# untitledunfinished.net
KiCad netlist of a schematic drawn in EAGLE
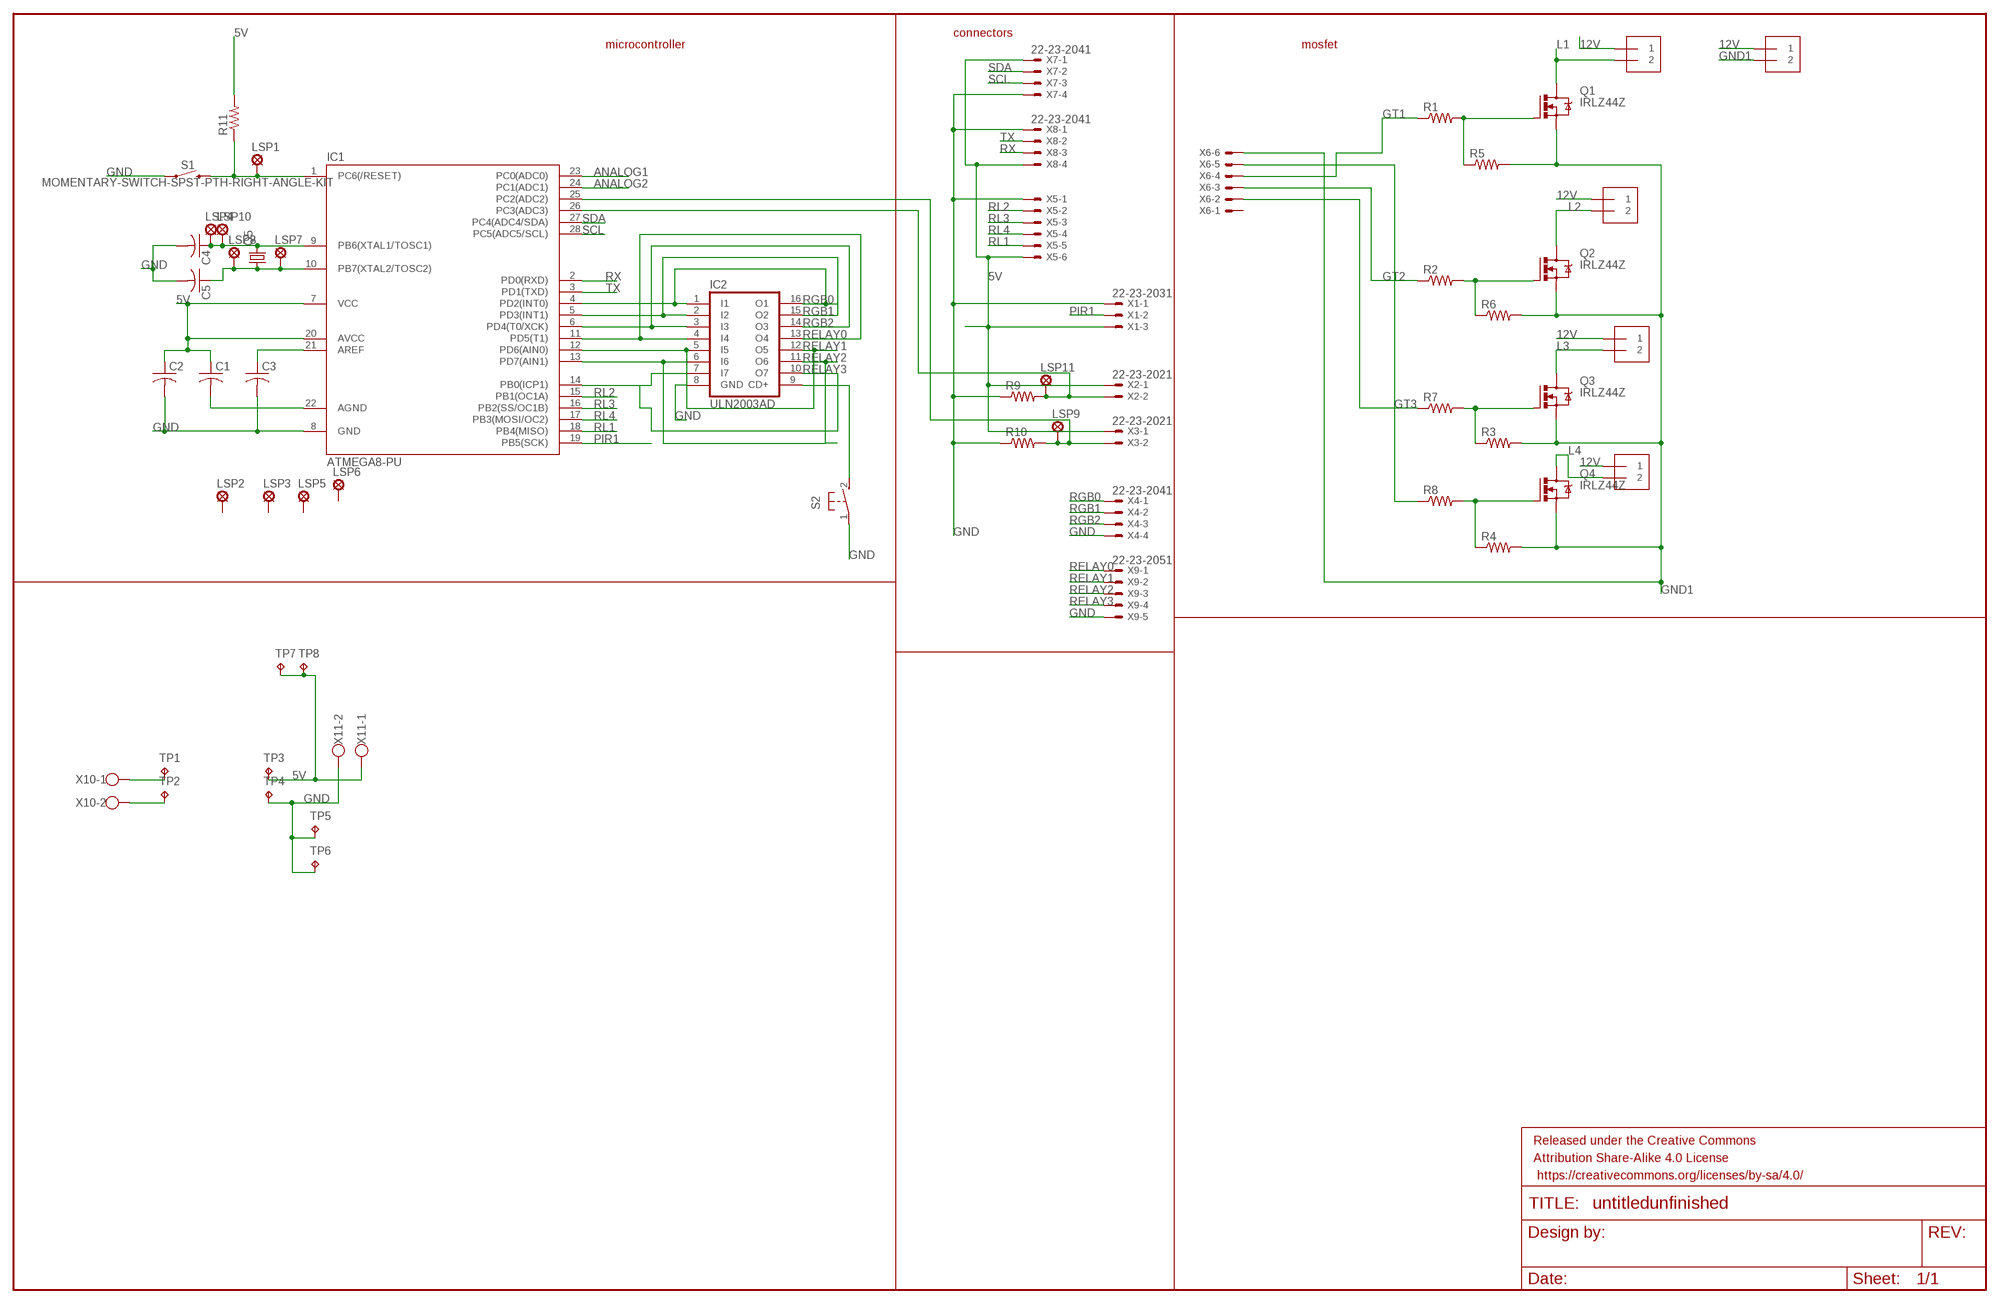
[diagram p0: schematic, sheet 1]

(export (version "E")
  (design (tool "Eeschema 10.0.6"))
  (components
    (comp (ref "C1")
      (value "C-US050-025X075")
      (footprint "eagle-import:C050-025X075")
      (libsource (lib "eagle-import") (part "C-US050-025X075"))
    )
    (comp (ref "C2")
      (value "C-US050-025X075")
      (footprint "eagle-import:C050-025X075")
      (libsource (lib "eagle-import") (part "C-US050-025X075"))
    )
    (comp (ref "C3")
      (value "C-US050-025X075")
      (footprint "eagle-import:C050-025X075")
      (libsource (lib "eagle-import") (part "C-US050-025X075"))
    )
    (comp (ref "C4")
      (value "C-US050-024X044")
      (footprint "eagle-import:C050-024X044")
      (libsource (lib "eagle-import") (part "C-US050-024X044"))
    )
    (comp (ref "C5")
      (value "C-US050-024X044")
      (footprint "eagle-import:C050-024X044")
      (libsource (lib "eagle-import") (part "C-US050-024X044"))
    )
    (comp (ref "FRAME1")
      (value "FRAME-LEDGER")
      (footprint "eagle-import:CREATIVE_COMMONS")
      (libsource (lib "eagle-import") (part "FRAME-LEDGER"))
    )
    (comp (ref "IC1")
      (value "ATMEGA8-PU")
      (footprint "eagle-import:DIL28-3")
      (libsource (lib "eagle-import") (part "ATMEGA8-PU"))
    )
    (comp (ref "IC2")
      (value "ULN2003AD")
      (footprint "eagle-import:SO16")
      (libsource (lib "eagle-import") (part "ULN2003AD"))
    )
    (comp (ref "J1")
      (value "1X2-3.5MM")
      (footprint "eagle-import:1X2-3.5MM")
      (libsource (lib "eagle-import") (part "1X2-3.5MM"))
    )
    (comp (ref "J2")
      (value "1X2-3.5MM")
      (footprint "eagle-import:1X2-3.5MM")
      (libsource (lib "eagle-import") (part "1X2-3.5MM"))
    )
    (comp (ref "J3")
      (value "1X2-3.5MM")
      (footprint "eagle-import:1X2-3.5MM")
      (libsource (lib "eagle-import") (part "1X2-3.5MM"))
    )
    (comp (ref "J4")
      (value "1X2-3.5MM")
      (footprint "eagle-import:1X2-3.5MM")
      (libsource (lib "eagle-import") (part "1X2-3.5MM"))
    )
    (comp (ref "J5")
      (value "1X2-3.5MM")
      (footprint "eagle-import:1X2-3.5MM")
      (libsource (lib "eagle-import") (part "1X2-3.5MM"))
    )
    (comp (ref "LSP1")
      (value "SE11")
      (footprint "eagle-import:SE11")
      (libsource (lib "eagle-import") (part "SE11"))
    )
    (comp (ref "LSP2")
      (value "SE11")
      (footprint "eagle-import:SE11")
      (libsource (lib "eagle-import") (part "SE11"))
    )
    (comp (ref "LSP3")
      (value "SE11")
      (footprint "eagle-import:SE11")
      (libsource (lib "eagle-import") (part "SE11"))
    )
    (comp (ref "LSP4")
      (value "SE11")
      (footprint "eagle-import:SE11")
      (libsource (lib "eagle-import") (part "SE11"))
    )
    (comp (ref "LSP5")
      (value "SE11")
      (footprint "eagle-import:SE11")
      (libsource (lib "eagle-import") (part "SE11"))
    )
    (comp (ref "LSP6")
      (value "SE11")
      (footprint "eagle-import:SE11")
      (libsource (lib "eagle-import") (part "SE11"))
    )
    (comp (ref "LSP7")
      (value "SE11")
      (footprint "eagle-import:SE11")
      (libsource (lib "eagle-import") (part "SE11"))
    )
    (comp (ref "LSP8")
      (value "SE11")
      (footprint "eagle-import:SE11")
      (libsource (lib "eagle-import") (part "SE11"))
    )
    (comp (ref "LSP9")
      (value "SE11")
      (footprint "eagle-import:SE11")
      (libsource (lib "eagle-import") (part "SE11"))
    )
    (comp (ref "LSP10")
      (value "SE11")
      (footprint "eagle-import:SE11")
      (libsource (lib "eagle-import") (part "SE11"))
    )
    (comp (ref "LSP11")
      (value "SE11")
      (footprint "eagle-import:SE11")
      (libsource (lib "eagle-import") (part "SE11"))
    )
    (comp (ref "Q1")
      (value "IRLZ44Z")
      (footprint "eagle-import:TO220BH")
      (libsource (lib "eagle-import") (part "IRLZ44Z"))
    )
    (comp (ref "Q2")
      (value "IRLZ44Z")
      (footprint "eagle-import:TO220BH")
      (libsource (lib "eagle-import") (part "IRLZ44Z"))
    )
    (comp (ref "Q3")
      (value "IRLZ44Z")
      (footprint "eagle-import:TO220BH")
      (libsource (lib "eagle-import") (part "IRLZ44Z"))
    )
    (comp (ref "Q4")
      (value "IRLZ44Z")
      (footprint "eagle-import:TO220BH")
      (libsource (lib "eagle-import") (part "IRLZ44Z"))
    )
    (comp (ref "Q5")
      (value "CRYSTALHC49U-V")
      (footprint "eagle-import:HC49U-V")
      (libsource (lib "eagle-import") (part "CRYSTALHC49U-V"))
    )
    (comp (ref "R1")
      (value "R-US_0207/10")
      (footprint "eagle-import:0207_10")
      (libsource (lib "eagle-import") (part "R-US_0207/10"))
    )
    (comp (ref "R2")
      (value "R-US_0207/10")
      (footprint "eagle-import:0207_10")
      (libsource (lib "eagle-import") (part "R-US_0207/10"))
    )
    (comp (ref "R3")
      (value "R-US_0207/10")
      (footprint "eagle-import:0207_10")
      (libsource (lib "eagle-import") (part "R-US_0207/10"))
    )
    (comp (ref "R4")
      (value "R-US_0207/10")
      (footprint "eagle-import:0207_10")
      (libsource (lib "eagle-import") (part "R-US_0207/10"))
    )
    (comp (ref "R5")
      (value "R-US_0207/10")
      (footprint "eagle-import:0207_10")
      (libsource (lib "eagle-import") (part "R-US_0207/10"))
    )
    (comp (ref "R6")
      (value "R-US_0207/10")
      (footprint "eagle-import:0207_10")
      (libsource (lib "eagle-import") (part "R-US_0207/10"))
    )
    (comp (ref "R7")
      (value "R-US_0207/10")
      (footprint "eagle-import:0207_10")
      (libsource (lib "eagle-import") (part "R-US_0207/10"))
    )
    (comp (ref "R8")
      (value "R-US_0207/10")
      (footprint "eagle-import:0207_10")
      (libsource (lib "eagle-import") (part "R-US_0207/10"))
    )
    (comp (ref "R9")
      (value "R-US_0207/15")
      (footprint "eagle-import:0207_15")
      (libsource (lib "eagle-import") (part "R-US_0207/15"))
    )
    (comp (ref "R10")
      (value "R-US_0207/15")
      (footprint "eagle-import:0207_15")
      (libsource (lib "eagle-import") (part "R-US_0207/15"))
    )
    (comp (ref "R11")
      (value "R-US_0207/10")
      (footprint "eagle-import:0207_10")
      (libsource (lib "eagle-import") (part "R-US_0207/10"))
    )
    (comp (ref "S1")
      (value "MOMENTARY-SWITCH-SPST-PTH-RIGHT-ANGLE-KIT")
      (footprint "eagle-import:TACTILE_SWITCH_PTH_RIGHT_ANGLE_KIT")
      (libsource (lib "eagle-import") (part "MOMENTARY-SWITCH-SPST-PTH-RIGHT-ANGLE-KIT"))
    )
    (comp (ref "S2")
      (value "31-XX")
      (footprint "eagle-import:B3F-31XX")
      (libsource (lib "eagle-import") (part "31-XX"))
    )
    (comp (ref "TP1")
      (value "TPPAD1-20Y")
      (footprint "eagle-import:P1-20Y")
      (libsource (lib "eagle-import") (part "TPPAD1-20Y"))
    )
    (comp (ref "TP2")
      (value "TPPAD1-20Y")
      (footprint "eagle-import:P1-20Y")
      (libsource (lib "eagle-import") (part "TPPAD1-20Y"))
    )
    (comp (ref "TP3")
      (value "TPPAD1-20Y")
      (footprint "eagle-import:P1-20Y")
      (libsource (lib "eagle-import") (part "TPPAD1-20Y"))
    )
    (comp (ref "TP4")
      (value "TPPAD1-20Y")
      (footprint "eagle-import:P1-20Y")
      (libsource (lib "eagle-import") (part "TPPAD1-20Y"))
    )
    (comp (ref "TP5")
      (value "TPPAD1-13Y")
      (footprint "eagle-import:P1-13Y")
      (libsource (lib "eagle-import") (part "TPPAD1-13Y"))
    )
    (comp (ref "TP6")
      (value "TPPAD1-13Y")
      (footprint "eagle-import:P1-13Y")
      (libsource (lib "eagle-import") (part "TPPAD1-13Y"))
    )
    (comp (ref "TP7")
      (value "TPPAD1-13Y")
      (footprint "eagle-import:P1-13Y")
      (libsource (lib "eagle-import") (part "TPPAD1-13Y"))
    )
    (comp (ref "TP8")
      (value "TPPAD1-13Y")
      (footprint "eagle-import:P1-13Y")
      (libsource (lib "eagle-import") (part "TPPAD1-13Y"))
    )
    (comp (ref "X1")
      (value "22-23-2031")
      (footprint "eagle-import:22-23-2031")
      (fields (field (name "MF") "MOLEX"))
      (libsource (lib "eagle-import") (part "22-23-2031"))
    )
    (comp (ref "X2")
      (value "22-23-2021")
      (footprint "eagle-import:22-23-2021")
      (fields (field (name "MF") "MOLEX"))
      (libsource (lib "eagle-import") (part "22-23-2021"))
    )
    (comp (ref "X3")
      (value "22-23-2021")
      (footprint "eagle-import:22-23-2021")
      (fields (field (name "MF") "MOLEX"))
      (libsource (lib "eagle-import") (part "22-23-2021"))
    )
    (comp (ref "X4")
      (value "22-23-2041")
      (footprint "eagle-import:22-23-2041")
      (fields (field (name "MF") "MOLEX"))
      (libsource (lib "eagle-import") (part "22-23-2041"))
    )
    (comp (ref "X5")
      (value "22-23-2061")
      (footprint "eagle-import:22-23-2061")
      (fields (field (name "MF") "MOLEX"))
      (libsource (lib "eagle-import") (part "22-23-2061"))
    )
    (comp (ref "X6")
      (value "22-23-2061")
      (footprint "eagle-import:22-23-2061")
      (fields (field (name "MF") "MOLEX"))
      (libsource (lib "eagle-import") (part "22-23-2061"))
    )
    (comp (ref "X7")
      (value "22-23-2041")
      (footprint "eagle-import:22-23-2041")
      (fields (field (name "MF") "MOLEX"))
      (libsource (lib "eagle-import") (part "22-23-2041"))
    )
    (comp (ref "X8")
      (value "22-23-2041")
      (footprint "eagle-import:22-23-2041")
      (fields (field (name "MF") "MOLEX"))
      (libsource (lib "eagle-import") (part "22-23-2041"))
    )
    (comp (ref "X9")
      (value "22-23-2051")
      (footprint "eagle-import:22-23-2051")
      (fields (field (name "MF") "MOLEX"))
      (libsource (lib "eagle-import") (part "22-23-2051"))
    )
    (comp (ref "X10")
      (value "W237-102")
      (footprint "eagle-import:W237-102")
      (fields (field (name "MPN") "237-102"))
      (libsource (lib "eagle-import") (part "W237-102"))
    )
    (comp (ref "X11")
      (value "W237-102")
      (footprint "eagle-import:W237-102")
      (fields (field (name "MPN") "237-102"))
      (libsource (lib "eagle-import") (part "W237-102"))
    )
  )
  (nets
    (net (code "1") (name "/5V") (class "Default")
      (node (ref "C1") (pin "1") (pinfunction "1_1") (pintype "passive"))
      (node (ref "C2") (pin "1") (pinfunction "1_1") (pintype "passive"))
      (node (ref "IC1") (pin "20") (pinfunction "AVCC_20") (pintype "passive"))
      (node (ref "IC1") (pin "7") (pinfunction "VCC_7") (pintype "power_in"))
      (node (ref "R11") (pin "2") (pinfunction "2_2") (pintype "passive"))
      (node (ref "TP3") (pin "TP") (pinfunction "TP_TP") (pintype "input"))
      (node (ref "TP7") (pin "TP") (pinfunction "TP_TP") (pintype "input"))
      (node (ref "TP8") (pin "TP") (pinfunction "TP_TP") (pintype "input"))
      (node (ref "X1") (pin "3") (pinfunction "S_3") (pintype "passive"))
      (node (ref "X11") (pin "1") (pinfunction "KL_1") (pintype "passive"))
      (node (ref "X2") (pin "1") (pinfunction "S_1") (pintype "passive"))
      (node (ref "X3") (pin "1") (pinfunction "S_1") (pintype "passive"))
      (node (ref "X5") (pin "6") (pinfunction "S_6") (pintype "passive"))
      (node (ref "X7") (pin "1") (pinfunction "S_1") (pintype "passive"))
      (node (ref "X8") (pin "4") (pinfunction "S_4") (pintype "passive"))
    )
    (net (code "2") (name "/12V") (class "Default")
      (node (ref "J1") (pin "1") (pinfunction "1_1") (pintype "passive"))
      (node (ref "J2") (pin "1") (pinfunction "1_1") (pintype "passive"))
      (node (ref "J3") (pin "1") (pinfunction "1_1") (pintype "passive"))
      (node (ref "J4") (pin "1") (pinfunction "1_1") (pintype "passive"))
      (node (ref "J5") (pin "1") (pinfunction "1_1") (pintype "passive"))
    )
    (net (code "3") (name "/ANALOG1") (class "Default")
      (node (ref "IC1") (pin "23") (pinfunction "PC0(ADC0)_23") (pintype "bidirectional"))
    )
    (net (code "4") (name "/ANALOG2") (class "Default")
      (node (ref "IC1") (pin "24") (pinfunction "PC1(ADC1)_24") (pintype "bidirectional"))
    )
    (net (code "5") (name "/GND") (class "Default")
      (node (ref "C2") (pin "2") (pinfunction "2_2") (pintype "passive"))
      (node (ref "C3") (pin "2") (pinfunction "2_2") (pintype "passive"))
      (node (ref "C4") (pin "2") (pinfunction "2_2") (pintype "passive"))
      (node (ref "C5") (pin "2") (pinfunction "2_2") (pintype "passive"))
      (node (ref "IC1") (pin "8") (pinfunction "GND_8") (pintype "power_in"))
      (node (ref "IC2") (pin "8") (pinfunction "GND_8") (pintype "power_in"))
      (node (ref "R10") (pin "1") (pinfunction "1_1") (pintype "passive"))
      (node (ref "R9") (pin "1") (pinfunction "1_1") (pintype "passive"))
      (node (ref "S1") (pin "1") (pinfunction "1_1") (pintype "passive"))
      (node (ref "S2") (pin "1") (pinfunction "P_1") (pintype "passive"))
      (node (ref "TP4") (pin "TP") (pinfunction "TP_TP") (pintype "input"))
      (node (ref "TP5") (pin "TP") (pinfunction "TP_TP") (pintype "input"))
      (node (ref "TP6") (pin "TP") (pinfunction "TP_TP") (pintype "input"))
      (node (ref "X1") (pin "1") (pinfunction "S_1") (pintype "passive"))
      (node (ref "X11") (pin "2") (pinfunction "KL_2") (pintype "passive"))
      (node (ref "X4") (pin "4") (pinfunction "S_4") (pintype "passive"))
      (node (ref "X5") (pin "1") (pinfunction "S_1") (pintype "passive"))
      (node (ref "X7") (pin "4") (pinfunction "S_4") (pintype "passive"))
      (node (ref "X8") (pin "1") (pinfunction "S_1") (pintype "passive"))
      (node (ref "X9") (pin "5") (pinfunction "S_5") (pintype "passive"))
    )
    (net (code "6") (name "/GND1") (class "Default")
      (node (ref "J5") (pin "2") (pinfunction "2_2") (pintype "passive"))
      (node (ref "Q1") (pin "S") (pinfunction "S_S") (pintype "passive"))
      (node (ref "Q2") (pin "S") (pinfunction "S_S") (pintype "passive"))
      (node (ref "Q3") (pin "S") (pinfunction "S_S") (pintype "passive"))
      (node (ref "Q4") (pin "S") (pinfunction "S_S") (pintype "passive"))
      (node (ref "R3") (pin "2") (pinfunction "2_2") (pintype "passive"))
      (node (ref "R4") (pin "2") (pinfunction "2_2") (pintype "passive"))
      (node (ref "R5") (pin "2") (pinfunction "2_2") (pintype "passive"))
      (node (ref "R6") (pin "2") (pinfunction "2_2") (pintype "passive"))
      (node (ref "X6") (pin "6") (pinfunction "S_6") (pintype "passive"))
    )
    (net (code "7") (name "/GT1") (class "Default")
      (node (ref "R1") (pin "1") (pinfunction "1_1") (pintype "passive"))
      (node (ref "X6") (pin "4") (pinfunction "S_4") (pintype "passive"))
    )
    (net (code "8") (name "/GT2") (class "Default")
      (node (ref "R2") (pin "1") (pinfunction "1_1") (pintype "passive"))
      (node (ref "X6") (pin "3") (pinfunction "S_3") (pintype "passive"))
    )
    (net (code "9") (name "/GT3") (class "Default")
      (node (ref "R7") (pin "1") (pinfunction "1_1") (pintype "passive"))
      (node (ref "X6") (pin "2") (pinfunction "S_2") (pintype "passive"))
    )
    (net (code "10") (name "/L1") (class "Default")
      (node (ref "J1") (pin "2") (pinfunction "2_2") (pintype "passive"))
      (node (ref "Q1") (pin "D") (pinfunction "D_D") (pintype "passive"))
    )
    (net (code "11") (name "/L2") (class "Default")
      (node (ref "J2") (pin "2") (pinfunction "2_2") (pintype "passive"))
      (node (ref "Q2") (pin "D") (pinfunction "D_D") (pintype "passive"))
    )
    (net (code "12") (name "/L3") (class "Default")
      (node (ref "J3") (pin "2") (pinfunction "2_2") (pintype "passive"))
      (node (ref "Q3") (pin "D") (pinfunction "D_D") (pintype "passive"))
    )
    (net (code "13") (name "/L4") (class "Default")
      (node (ref "J4") (pin "2") (pinfunction "2_2") (pintype "passive"))
      (node (ref "Q4") (pin "D") (pinfunction "D_D") (pintype "passive"))
    )
    (net (code "14") (name "/PIR1") (class "Default")
      (node (ref "IC1") (pin "19") (pinfunction "PB5(SCK)_19") (pintype "bidirectional"))
      (node (ref "X1") (pin "2") (pinfunction "S_2") (pintype "passive"))
    )
    (net (code "15") (name "/RELAY0") (class "Default")
      (node (ref "IC1") (pin "11") (pinfunction "PD5(T1)_11") (pintype "bidirectional"))
      (node (ref "IC2") (pin "13") (pinfunction "O4_13") (pintype "open_collector"))
      (node (ref "IC2") (pin "4") (pinfunction "I4_4") (pintype "input"))
      (node (ref "X9") (pin "1") (pinfunction "S_1") (pintype "passive"))
    )
    (net (code "16") (name "/RELAY1") (class "Default")
      (node (ref "IC1") (pin "12") (pinfunction "PD6(AIN0)_12") (pintype "bidirectional"))
      (node (ref "IC2") (pin "12") (pinfunction "O5_12") (pintype "open_collector"))
      (node (ref "IC2") (pin "5") (pinfunction "I5_5") (pintype "input"))
      (node (ref "X9") (pin "2") (pinfunction "S_2") (pintype "passive"))
    )
    (net (code "17") (name "/RELAY2") (class "Default")
      (node (ref "IC1") (pin "13") (pinfunction "PD7(AIN1)_13") (pintype "bidirectional"))
      (node (ref "IC2") (pin "11") (pinfunction "O6_11") (pintype "open_collector"))
      (node (ref "IC2") (pin "6") (pinfunction "I6_6") (pintype "input"))
      (node (ref "X9") (pin "3") (pinfunction "S_3") (pintype "passive"))
    )
    (net (code "18") (name "/RELAY3") (class "Default")
      (node (ref "IC1") (pin "14") (pinfunction "PB0(ICP1)_14") (pintype "bidirectional"))
      (node (ref "IC2") (pin "10") (pinfunction "O7_10") (pintype "open_collector"))
      (node (ref "IC2") (pin "7") (pinfunction "I7_7") (pintype "input"))
      (node (ref "X9") (pin "4") (pinfunction "S_4") (pintype "passive"))
    )
    (net (code "19") (name "/RGB0") (class "Default")
      (node (ref "IC1") (pin "4") (pinfunction "PD2(INT0)_4") (pintype "bidirectional"))
      (node (ref "IC2") (pin "1") (pinfunction "I1_1") (pintype "input"))
      (node (ref "IC2") (pin "16") (pinfunction "O1_16") (pintype "open_collector"))
      (node (ref "X4") (pin "1") (pinfunction "S_1") (pintype "passive"))
    )
    (net (code "20") (name "/RGB1") (class "Default")
      (node (ref "IC1") (pin "5") (pinfunction "PD3(INT1)_5") (pintype "bidirectional"))
      (node (ref "IC2") (pin "15") (pinfunction "O2_15") (pintype "open_collector"))
      (node (ref "IC2") (pin "2") (pinfunction "I2_2") (pintype "input"))
      (node (ref "X4") (pin "2") (pinfunction "S_2") (pintype "passive"))
    )
    (net (code "21") (name "/RGB2") (class "Default")
      (node (ref "IC1") (pin "6") (pinfunction "PD4(T0/XCK)_6") (pintype "bidirectional"))
      (node (ref "IC2") (pin "14") (pinfunction "O3_14") (pintype "open_collector"))
      (node (ref "IC2") (pin "3") (pinfunction "I3_3") (pintype "input"))
      (node (ref "X4") (pin "3") (pinfunction "S_3") (pintype "passive"))
    )
    (net (code "22") (name "/RL1") (class "Default")
      (node (ref "IC1") (pin "18") (pinfunction "PB4(MISO)_18") (pintype "bidirectional"))
      (node (ref "X5") (pin "5") (pinfunction "S_5") (pintype "passive"))
    )
    (net (code "23") (name "/RL2") (class "Default")
      (node (ref "IC1") (pin "15") (pinfunction "PB1(OC1A)_15") (pintype "bidirectional"))
      (node (ref "X5") (pin "2") (pinfunction "S_2") (pintype "passive"))
    )
    (net (code "24") (name "/RL3") (class "Default")
      (node (ref "IC1") (pin "16") (pinfunction "PB2(SS/OC1B)_16") (pintype "bidirectional"))
      (node (ref "X5") (pin "3") (pinfunction "S_3") (pintype "passive"))
    )
    (net (code "25") (name "/RL4") (class "Default")
      (node (ref "IC1") (pin "17") (pinfunction "PB3(MOSI/OC2)_17") (pintype "bidirectional"))
      (node (ref "X5") (pin "4") (pinfunction "S_4") (pintype "passive"))
    )
    (net (code "26") (name "/RX") (class "Default")
      (node (ref "IC1") (pin "2") (pinfunction "PD0(RXD)_2") (pintype "bidirectional"))
      (node (ref "X8") (pin "3") (pinfunction "S_3") (pintype "passive"))
    )
    (net (code "27") (name "/SCL") (class "Default")
      (node (ref "IC1") (pin "28") (pinfunction "PC5(ADC5/SCL)_28") (pintype "bidirectional"))
      (node (ref "X7") (pin "3") (pinfunction "S_3") (pintype "passive"))
    )
    (net (code "28") (name "/SDA") (class "Default")
      (node (ref "IC1") (pin "27") (pinfunction "PC4(ADC4/SDA)_27") (pintype "bidirectional"))
      (node (ref "X7") (pin "2") (pinfunction "S_2") (pintype "passive"))
    )
    (net (code "29") (name "/TX") (class "Default")
      (node (ref "IC1") (pin "3") (pinfunction "PD1(TXD)_3") (pintype "bidirectional"))
      (node (ref "X8") (pin "2") (pinfunction "S_2") (pintype "passive"))
    )
    (net (code "30") (name "Net-(IC1-AGND)") (class "Default")
      (node (ref "C1") (pin "2") (pinfunction "2_2") (pintype "passive"))
      (node (ref "IC1") (pin "22") (pinfunction "AGND_22") (pintype "power_in"))
    )
    (net (code "31") (name "Net-(IC1-AREF)") (class "Default")
      (node (ref "C3") (pin "1") (pinfunction "1_1") (pintype "passive"))
      (node (ref "IC1") (pin "21") (pinfunction "AREF_21") (pintype "passive"))
    )
    (net (code "32") (name "Net-(IC1-PB6(XTAL1{slash}TOSC1))") (class "Default")
      (node (ref "C4") (pin "1") (pinfunction "1_1") (pintype "passive"))
      (node (ref "IC1") (pin "9") (pinfunction "PB6(XTAL1/TOSC1)_9") (pintype "bidirectional"))
      (node (ref "LSP10") (pin "MP") (pinfunction "MP_MP") (pintype "passive"))
      (node (ref "LSP4") (pin "MP") (pinfunction "MP_MP") (pintype "passive"))
      (node (ref "Q5") (pin "2") (pinfunction "2_2") (pintype "passive"))
    )
    (net (code "33") (name "Net-(IC1-PB7(XTAL2{slash}TOSC2))") (class "Default")
      (node (ref "C5") (pin "1") (pinfunction "1_1") (pintype "passive"))
      (node (ref "IC1") (pin "10") (pinfunction "PB7(XTAL2/TOSC2)_10") (pintype "bidirectional"))
      (node (ref "LSP7") (pin "MP") (pinfunction "MP_MP") (pintype "passive"))
      (node (ref "LSP8") (pin "MP") (pinfunction "MP_MP") (pintype "passive"))
      (node (ref "Q5") (pin "1") (pinfunction "1_1") (pintype "passive"))
    )
    (net (code "34") (name "Net-(IC1-PC2(ADC2))") (class "Default")
      (node (ref "IC1") (pin "25") (pinfunction "PC2(ADC2)_25") (pintype "bidirectional"))
      (node (ref "LSP9") (pin "MP") (pinfunction "MP_MP") (pintype "passive"))
      (node (ref "R10") (pin "2") (pinfunction "2_2") (pintype "passive"))
      (node (ref "X3") (pin "2") (pinfunction "S_2") (pintype "passive"))
    )
    (net (code "35") (name "Net-(IC1-PC3(ADC3))") (class "Default")
      (node (ref "IC1") (pin "26") (pinfunction "PC3(ADC3)_26") (pintype "bidirectional"))
      (node (ref "LSP11") (pin "MP") (pinfunction "MP_MP") (pintype "passive"))
      (node (ref "R9") (pin "2") (pinfunction "2_2") (pintype "passive"))
      (node (ref "X2") (pin "2") (pinfunction "S_2") (pintype "passive"))
    )
    (net (code "36") (name "Net-(IC1-PC6({slash}RESET))") (class "Default")
      (node (ref "IC1") (pin "1") (pinfunction "PC6(/RESET)_1") (pintype "bidirectional"))
      (node (ref "LSP1") (pin "MP") (pinfunction "MP_MP") (pintype "passive"))
      (node (ref "R11") (pin "1") (pinfunction "1_1") (pintype "passive"))
      (node (ref "S1") (pin "2") (pinfunction "2_2") (pintype "passive"))
    )
    (net (code "37") (name "Net-(IC2-CD+)") (class "Default")
      (node (ref "IC2") (pin "9") (pinfunction "CD+_9") (pintype "passive"))
      (node (ref "S2") (pin "2") (pinfunction "S_2") (pintype "passive"))
    )
    (net (code "38") (name "Net-(Q1-PadG)") (class "Default")
      (node (ref "Q1") (pin "G") (pinfunction "G_G") (pintype "passive"))
      (node (ref "R1") (pin "2") (pinfunction "2_2") (pintype "passive"))
      (node (ref "R5") (pin "1") (pinfunction "1_1") (pintype "passive"))
    )
    (net (code "39") (name "Net-(Q2-PadG)") (class "Default")
      (node (ref "Q2") (pin "G") (pinfunction "G_G") (pintype "passive"))
      (node (ref "R2") (pin "2") (pinfunction "2_2") (pintype "passive"))
      (node (ref "R6") (pin "1") (pinfunction "1_1") (pintype "passive"))
    )
    (net (code "40") (name "Net-(Q3-PadG)") (class "Default")
      (node (ref "Q3") (pin "G") (pinfunction "G_G") (pintype "passive"))
      (node (ref "R3") (pin "1") (pinfunction "1_1") (pintype "passive"))
      (node (ref "R7") (pin "2") (pinfunction "2_2") (pintype "passive"))
    )
    (net (code "41") (name "Net-(Q4-PadG)") (class "Default")
      (node (ref "Q4") (pin "G") (pinfunction "G_G") (pintype "passive"))
      (node (ref "R4") (pin "1") (pinfunction "1_1") (pintype "passive"))
      (node (ref "R8") (pin "2") (pinfunction "2_2") (pintype "passive"))
    )
    (net (code "42") (name "Net-(X6E-S)") (class "Default")
      (node (ref "R8") (pin "1") (pinfunction "1_1") (pintype "passive"))
      (node (ref "X6") (pin "5") (pinfunction "S_5") (pintype "passive"))
    )
    (net (code "43") (name "Net-(X10A-KL)") (class "Default")
      (node (ref "TP1") (pin "TP") (pinfunction "TP_TP") (pintype "input"))
      (node (ref "X10") (pin "1") (pinfunction "KL_1") (pintype "passive"))
    )
    (net (code "44") (name "Net-(X10B-KL)") (class "Default")
      (node (ref "TP2") (pin "TP") (pinfunction "TP_TP") (pintype "input"))
      (node (ref "X10") (pin "2") (pinfunction "KL_2") (pintype "passive"))
    )
    (net (code "45") (name "unconnected-(LSP2-PadMP)") (class "Default")
      (node (ref "LSP2") (pin "MP") (pinfunction "MP_MP") (pintype "passive"))
    )
    (net (code "46") (name "unconnected-(LSP3-PadMP)") (class "Default")
      (node (ref "LSP3") (pin "MP") (pinfunction "MP_MP") (pintype "passive"))
    )
    (net (code "47") (name "unconnected-(LSP5-PadMP)") (class "Default")
      (node (ref "LSP5") (pin "MP") (pinfunction "MP_MP") (pintype "passive"))
    )
    (net (code "48") (name "unconnected-(LSP6-PadMP)") (class "Default")
      (node (ref "LSP6") (pin "MP") (pinfunction "MP_MP") (pintype "passive"))
    )
    (net (code "49") (name "unconnected-(X6A-S-Pad1)") (class "Default")
      (node (ref "X6") (pin "1") (pinfunction "S_1") (pintype "passive"))
    )
  )
)
